# 1-Schematic_motor_starter_pcb_design.net
KiCad netlist of a schematic drawn in EasyEDA
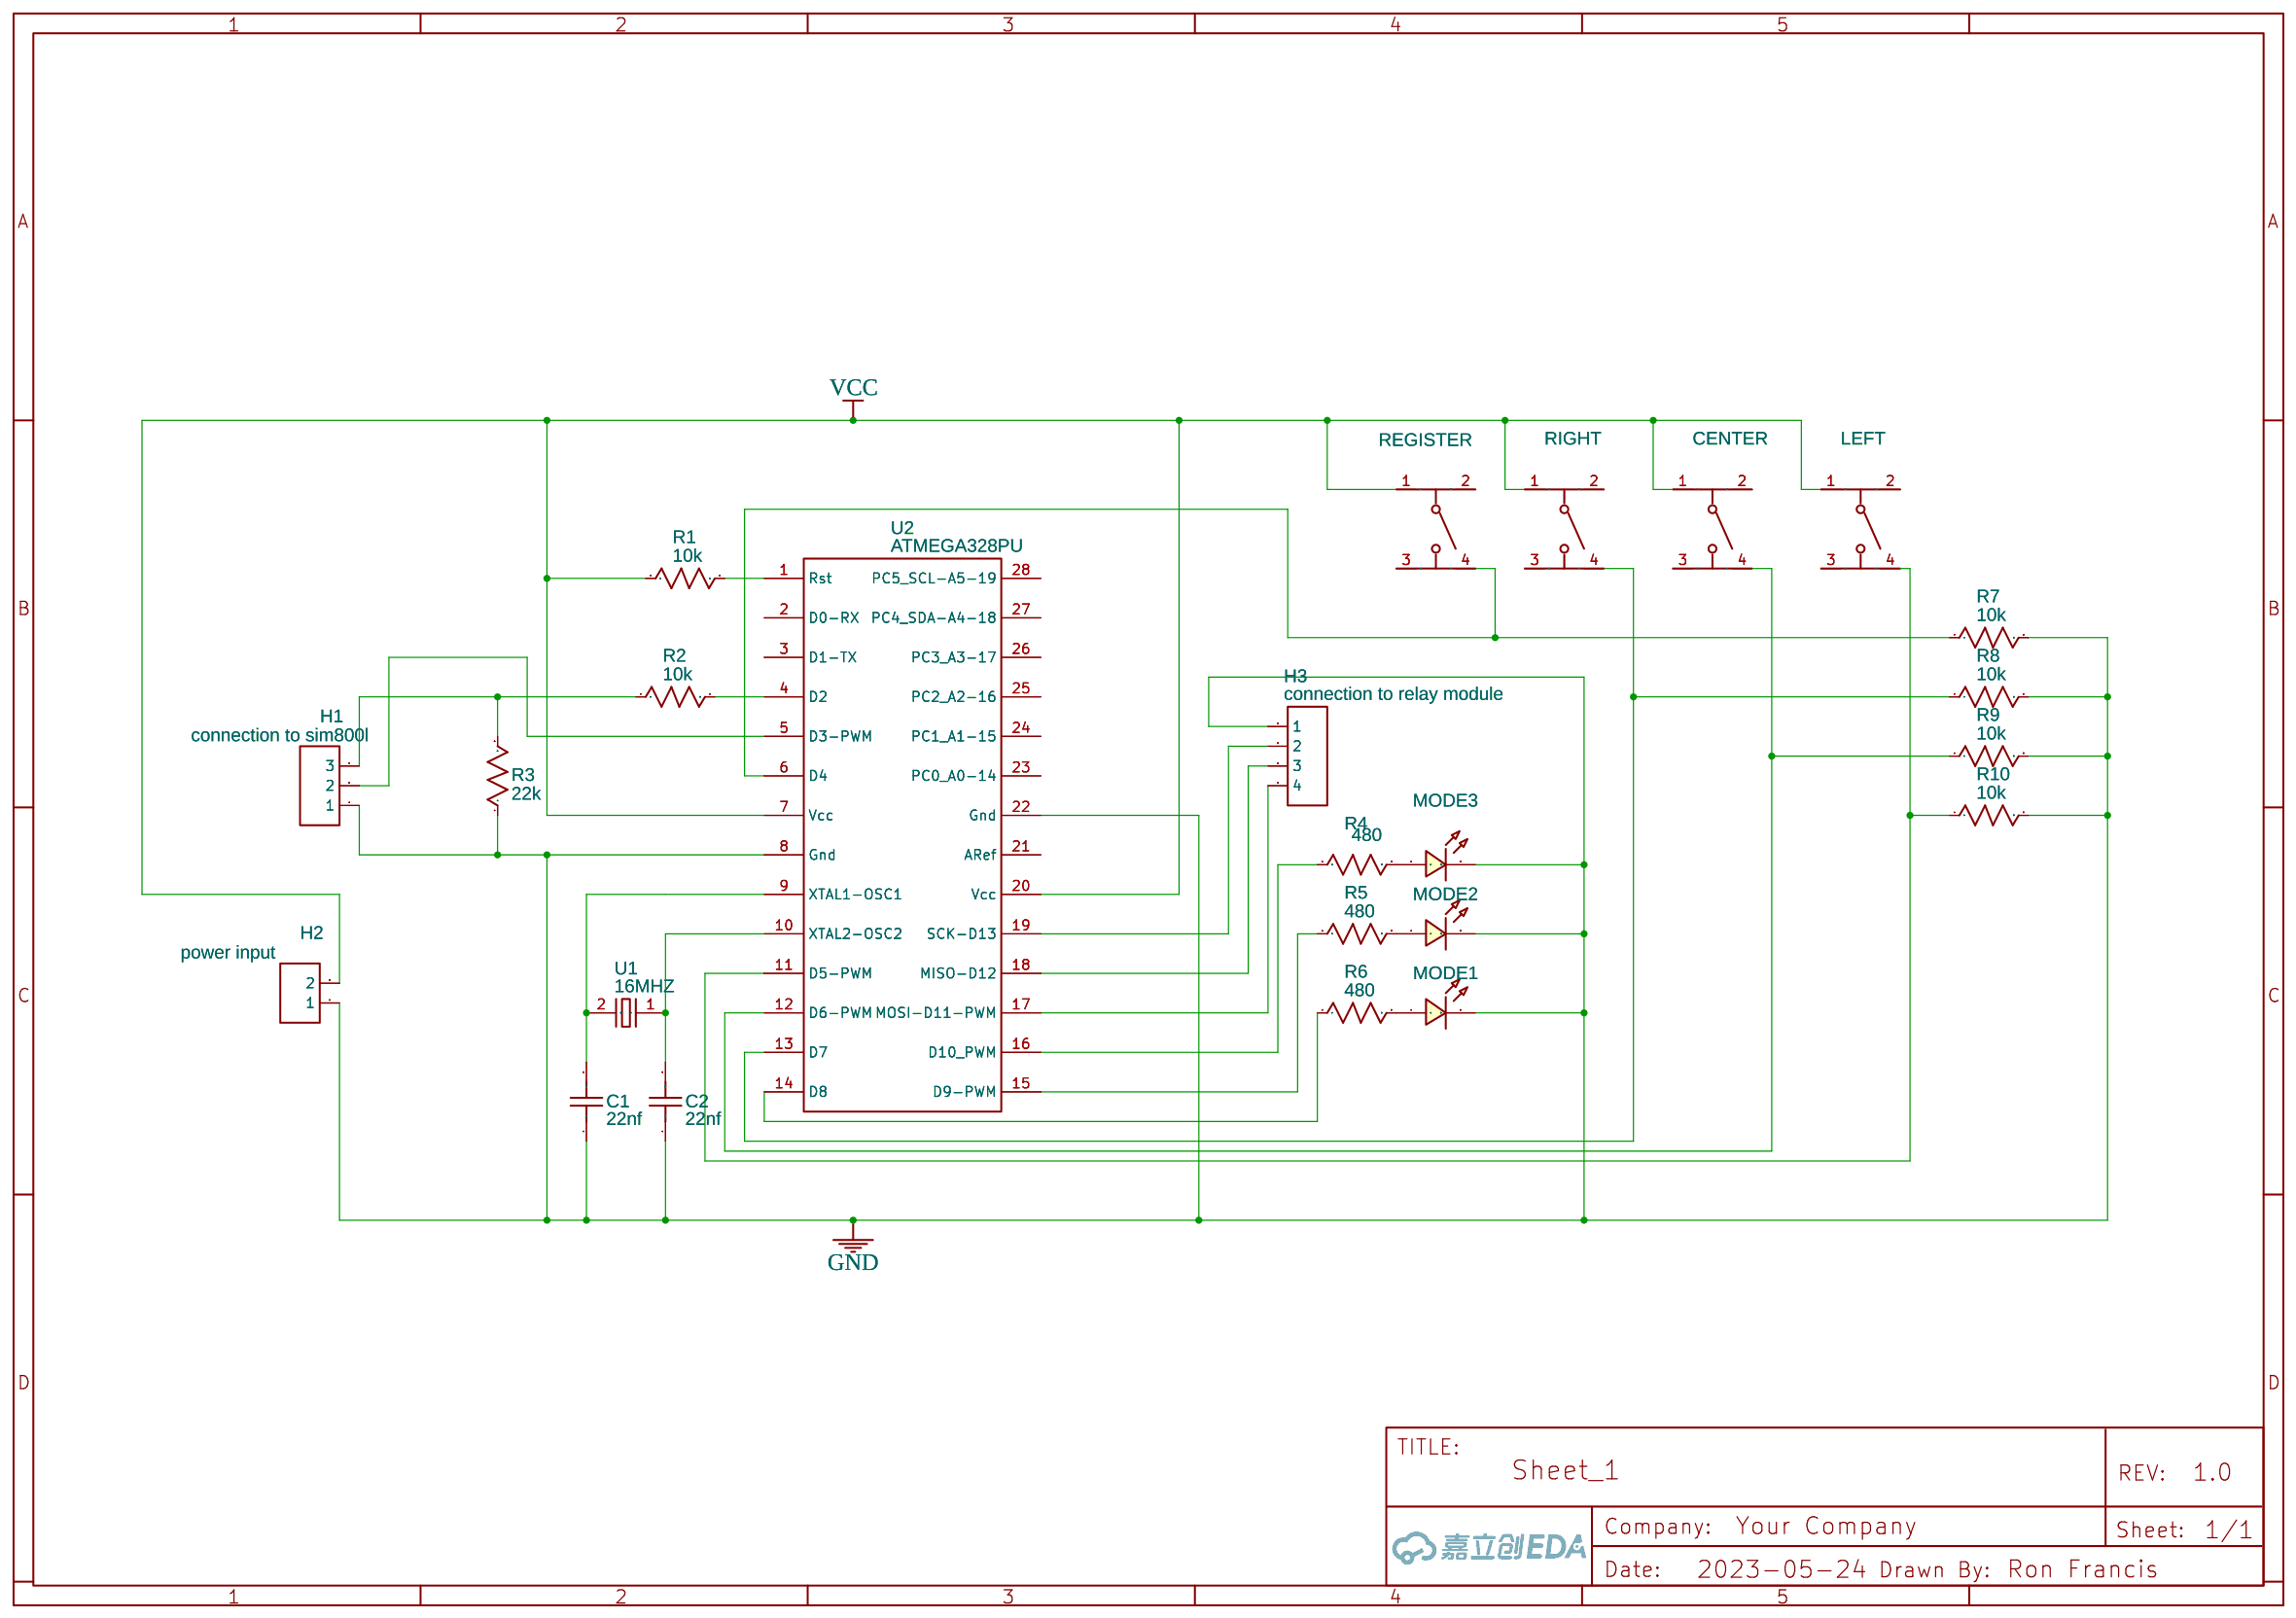
[diagram p0: schematic sheet]

(export (version "E")
  (design (tool "Eeschema 10.0.6"))
  (components
    (comp (ref "C1") (value "22nf") (libsource (lib "") (part "C_RAD-0.1_US")))
    (comp (ref "C2") (value "22nf") (libsource (lib "") (part "C_RAD-0.1_US")))
    (comp (ref "CENTER")
      (value "Button-SMD-6×6×5mm")
      (fields
        (field (name "BOM_Manufacturer Part") "6×6×5mm RHOS")
        (field (name "BOM_Supplier Part") "C21456")
      )
      (libsource (lib "") (part "Button-SMD-6×6×5mm_2"))
    )
    (comp (ref "H1")
      (value "connection to sim800l")
      (fields (field (name "BOM_Supplier Part") "C146690"))
      (libsource (lib "") (part "HDR-F-2.54_1x3"))
    )
    (comp (ref "H2")
      (value "power input")
      (fields (field (name "BOM_Supplier Part") "C49661"))
      (libsource (lib "") (part "HDR-F-2.54_1x2"))
    )
    (comp (ref "H3")
      (value "connection to relay module")
      (fields (field (name "BOM_Supplier Part") "C225501"))
      (libsource (lib "") (part "HDR-F-2.54_1x4"))
    )
    (comp (ref "LEFT")
      (value "Button-SMD-6×6×5mm")
      (fields
        (field (name "BOM_Manufacturer Part") "6×6×5mm RHOS")
        (field (name "BOM_Supplier Part") "C21456")
      )
      (libsource (lib "") (part "Button-SMD-6×6×5mm_1"))
    )
    (comp (ref "MODE1")
      (value "LED-TH-5mm_R")
      (fields
        (field (name "BOM_Manufacturer Part") "333-2SURD/S530-A3")
        (field (name "BOM_Supplier Part") "C87271")
      )
      (libsource (lib "") (part "LED-TH-5mm_R"))
    )
    (comp (ref "MODE2")
      (value "LED-TH-5mm_R")
      (fields
        (field (name "BOM_Manufacturer Part") "333-2SURD/S530-A3")
        (field (name "BOM_Supplier Part") "C87271")
      )
      (libsource (lib "") (part "LED-TH-5mm_R"))
    )
    (comp (ref "MODE3")
      (value "LED-TH-5mm_R")
      (fields
        (field (name "BOM_Manufacturer Part") "333-2SURD/S530-A3")
        (field (name "BOM_Supplier Part") "C87271")
      )
      (libsource (lib "") (part "LED-TH-5mm_R"))
    )
    (comp (ref "R1") (value "10k") (libsource (lib "") (part "R_AXIAL-0.4_US")))
    (comp (ref "R2") (value "10k") (libsource (lib "") (part "R_AXIAL-0.4_US")))
    (comp (ref "R3") (value "22k") (libsource (lib "") (part "R_AXIAL-0.4_US_1")))
    (comp (ref "R4") (value "480") (libsource (lib "") (part "R_AXIAL-0.4_US")))
    (comp (ref "R5") (value "480") (libsource (lib "") (part "R_AXIAL-0.4_US")))
    (comp (ref "R6") (value "480") (libsource (lib "") (part "R_AXIAL-0.4_US")))
    (comp (ref "R7") (value "10k") (libsource (lib "") (part "R_AXIAL-0.4_US")))
    (comp (ref "R8") (value "10k") (libsource (lib "") (part "R_AXIAL-0.4_US")))
    (comp (ref "R9") (value "10k") (libsource (lib "") (part "R_AXIAL-0.4_US")))
    (comp (ref "R10") (value "10k") (libsource (lib "") (part "R_AXIAL-0.4_US")))
    (comp (ref "REGISTER")
      (value "Button-SMD-6×6×5mm")
      (fields
        (field (name "BOM_Manufacturer Part") "6×6×5mm RHOS")
        (field (name "BOM_Supplier Part") "C21456")
      )
      (libsource (lib "") (part "Button-SMD-6×6×5mm"))
    )
    (comp (ref "RIGHT")
      (value "Button-SMD-6×6×5mm")
      (fields
        (field (name "BOM_Manufacturer Part") "6×6×5mm RHOS")
        (field (name "BOM_Supplier Part") "C21456")
      )
      (libsource (lib "") (part "Button-SMD-6×6×5mm_3"))
    )
    (comp (ref "U1")
      (value "16MHZ")
      (fields (field (name "BOM_Supplier Part") "C9900024699"))
      (libsource (lib "") (part "16MHZ_C9900024699"))
    )
    (comp (ref "U2") (value "ATMEGA328PU") (libsource (lib "") (part "ATMEGA328PU")))
  )
  (nets
    (net (code "1") (name "GND") (class "Default")
      (node (ref "C1") (pin "1") (pinfunction "1_1") (pintype "unspecified"))
      (node (ref "C2") (pin "1") (pinfunction "1_1") (pintype "unspecified"))
      (node (ref "H1") (pin "1") (pinfunction "1_1") (pintype "input"))
      (node (ref "H2") (pin "1") (pinfunction "1_1") (pintype "input"))
      (node (ref "H3") (pin "1") (pinfunction "1_1") (pintype "unspecified"))
      (node (ref "MODE1") (pin "2") (pinfunction "2_2") (pintype "unspecified"))
      (node (ref "MODE2") (pin "2") (pinfunction "2_2") (pintype "unspecified"))
      (node (ref "MODE3") (pin "2") (pinfunction "2_2") (pintype "unspecified"))
      (node (ref "R10") (pin "2") (pinfunction "2_2") (pintype "unspecified"))
      (node (ref "R3") (pin "1") (pinfunction "1_1") (pintype "unspecified"))
      (node (ref "R7") (pin "2") (pinfunction "2_2") (pintype "unspecified"))
      (node (ref "R8") (pin "2") (pinfunction "2_2") (pintype "unspecified"))
      (node (ref "R9") (pin "2") (pinfunction "2_2") (pintype "unspecified"))
      (node (ref "U2") (pin "22") (pinfunction "Gnd_22") (pintype "unspecified"))
      (node (ref "U2") (pin "8") (pinfunction "Gnd_8") (pintype "unspecified"))
    )
    (net (code "2") (name "Net-(H1-Pad3)") (class "Default")
      (node (ref "H1") (pin "3") (pinfunction "3_3") (pintype "input"))
      (node (ref "R2") (pin "1") (pinfunction "1_1") (pintype "unspecified"))
      (node (ref "R3") (pin "2") (pinfunction "2_2") (pintype "unspecified"))
    )
    (net (code "3") (name "Net-(MODE1-Pad1)") (class "Default")
      (node (ref "MODE1") (pin "1") (pinfunction "1_1") (pintype "unspecified"))
      (node (ref "R6") (pin "2") (pinfunction "2_2") (pintype "unspecified"))
    )
    (net (code "4") (name "Net-(MODE2-Pad1)") (class "Default")
      (node (ref "MODE2") (pin "1") (pinfunction "1_1") (pintype "unspecified"))
      (node (ref "R5") (pin "2") (pinfunction "2_2") (pintype "unspecified"))
    )
    (net (code "5") (name "Net-(MODE3-Pad1)") (class "Default")
      (node (ref "MODE3") (pin "1") (pinfunction "1_1") (pintype "unspecified"))
      (node (ref "R4") (pin "2") (pinfunction "2_2") (pintype "unspecified"))
    )
    (net (code "6") (name "Net-(U2-D2)") (class "Default")
      (node (ref "R2") (pin "2") (pinfunction "2_2") (pintype "unspecified"))
      (node (ref "U2") (pin "4") (pinfunction "D2_4") (pintype "unspecified"))
    )
    (net (code "7") (name "Net-(U2-D3-PWM)") (class "Default")
      (node (ref "H1") (pin "2") (pinfunction "2_2") (pintype "input"))
      (node (ref "U2") (pin "5") (pinfunction "D3-PWM_5") (pintype "unspecified"))
    )
    (net (code "8") (name "Net-(U2-D4)") (class "Default")
      (node (ref "R7") (pin "1") (pinfunction "1_1") (pintype "unspecified"))
      (node (ref "REGISTER") (pin "4") (pinfunction "4_4") (pintype "unspecified"))
      (node (ref "U2") (pin "6") (pinfunction "D4_6") (pintype "unspecified"))
    )
    (net (code "9") (name "Net-(U2-D5-PWM)") (class "Default")
      (node (ref "LEFT") (pin "4") (pinfunction "4_4") (pintype "unspecified"))
      (node (ref "R10") (pin "1") (pinfunction "1_1") (pintype "unspecified"))
      (node (ref "U2") (pin "11") (pinfunction "D5-PWM_11") (pintype "unspecified"))
    )
    (net (code "10") (name "Net-(U2-D6-PWM)") (class "Default")
      (node (ref "CENTER") (pin "4") (pinfunction "4_4") (pintype "unspecified"))
      (node (ref "R9") (pin "1") (pinfunction "1_1") (pintype "unspecified"))
      (node (ref "U2") (pin "12") (pinfunction "D6-PWM_12") (pintype "unspecified"))
    )
    (net (code "11") (name "Net-(U2-D7)") (class "Default")
      (node (ref "R8") (pin "1") (pinfunction "1_1") (pintype "unspecified"))
      (node (ref "RIGHT") (pin "4") (pinfunction "4_4") (pintype "unspecified"))
      (node (ref "U2") (pin "13") (pinfunction "D7_13") (pintype "unspecified"))
    )
    (net (code "12") (name "Net-(U2-D8)") (class "Default")
      (node (ref "R6") (pin "1") (pinfunction "1_1") (pintype "unspecified"))
      (node (ref "U2") (pin "14") (pinfunction "D8_14") (pintype "unspecified"))
    )
    (net (code "13") (name "Net-(U2-D9-PWM)") (class "Default")
      (node (ref "R5") (pin "1") (pinfunction "1_1") (pintype "unspecified"))
      (node (ref "U2") (pin "15") (pinfunction "D9-PWM_15") (pintype "unspecified"))
    )
    (net (code "14") (name "Net-(U2-D10_PWM)") (class "Default")
      (node (ref "R4") (pin "1") (pinfunction "1_1") (pintype "unspecified"))
      (node (ref "U2") (pin "16") (pinfunction "D10_PWM_16") (pintype "unspecified"))
    )
    (net (code "15") (name "Net-(U2-MISO-D12)") (class "Default")
      (node (ref "H3") (pin "3") (pinfunction "3_3") (pintype "unspecified"))
      (node (ref "U2") (pin "18") (pinfunction "MISO-D12_18") (pintype "unspecified"))
    )
    (net (code "16") (name "Net-(U2-MOSI-D11-PWM)") (class "Default")
      (node (ref "H3") (pin "4") (pinfunction "4_4") (pintype "unspecified"))
      (node (ref "U2") (pin "17") (pinfunction "MOSI-D11-PWM_17") (pintype "unspecified"))
    )
    (net (code "17") (name "Net-(U2-Rst)") (class "Default")
      (node (ref "R1") (pin "2") (pinfunction "2_2") (pintype "unspecified"))
      (node (ref "U2") (pin "1") (pinfunction "Rst_1") (pintype "unspecified"))
    )
    (net (code "18") (name "Net-(U2-SCK-D13)") (class "Default")
      (node (ref "H3") (pin "2") (pinfunction "2_2") (pintype "unspecified"))
      (node (ref "U2") (pin "19") (pinfunction "SCK-D13_19") (pintype "unspecified"))
    )
    (net (code "19") (name "Net-(U2-XTAL1-OSC1)") (class "Default")
      (node (ref "C1") (pin "2") (pinfunction "2_2") (pintype "unspecified"))
      (node (ref "U1") (pin "2") (pinfunction "2_2") (pintype "input"))
      (node (ref "U2") (pin "9") (pinfunction "XTAL1-OSC1_9") (pintype "unspecified"))
    )
    (net (code "20") (name "Net-(U2-XTAL2-OSC2)") (class "Default")
      (node (ref "C2") (pin "2") (pinfunction "2_2") (pintype "unspecified"))
      (node (ref "U1") (pin "1") (pinfunction "1_1") (pintype "input"))
      (node (ref "U2") (pin "10") (pinfunction "XTAL2-OSC2_10") (pintype "unspecified"))
    )
    (net (code "21") (name "VCC") (class "Default")
      (node (ref "CENTER") (pin "1") (pinfunction "1_1") (pintype "unspecified"))
      (node (ref "H2") (pin "2") (pinfunction "2_2") (pintype "input"))
      (node (ref "LEFT") (pin "1") (pinfunction "1_1") (pintype "unspecified"))
      (node (ref "R1") (pin "1") (pinfunction "1_1") (pintype "unspecified"))
      (node (ref "REGISTER") (pin "1") (pinfunction "1_1") (pintype "unspecified"))
      (node (ref "RIGHT") (pin "1") (pinfunction "1_1") (pintype "unspecified"))
      (node (ref "U2") (pin "20") (pinfunction "Vcc_20") (pintype "unspecified"))
      (node (ref "U2") (pin "7") (pinfunction "Vcc_7") (pintype "unspecified"))
    )
    (net (code "22") (name "unconnected-(CENTER-Pad2)") (class "Default")
      (node (ref "CENTER") (pin "2") (pinfunction "2_2") (pintype "unspecified"))
    )
    (net (code "23") (name "unconnected-(CENTER-Pad3)") (class "Default")
      (node (ref "CENTER") (pin "3") (pinfunction "3_3") (pintype "unspecified"))
    )
    (net (code "24") (name "unconnected-(LEFT-Pad2)") (class "Default")
      (node (ref "LEFT") (pin "2") (pinfunction "2_2") (pintype "unspecified"))
    )
    (net (code "25") (name "unconnected-(LEFT-Pad3)") (class "Default")
      (node (ref "LEFT") (pin "3") (pinfunction "3_3") (pintype "unspecified"))
    )
    (net (code "26") (name "unconnected-(REGISTER-Pad2)") (class "Default")
      (node (ref "REGISTER") (pin "2") (pinfunction "2_2") (pintype "unspecified"))
    )
    (net (code "27") (name "unconnected-(REGISTER-Pad3)") (class "Default")
      (node (ref "REGISTER") (pin "3") (pinfunction "3_3") (pintype "unspecified"))
    )
    (net (code "28") (name "unconnected-(RIGHT-Pad2)") (class "Default")
      (node (ref "RIGHT") (pin "2") (pinfunction "2_2") (pintype "unspecified"))
    )
    (net (code "29") (name "unconnected-(RIGHT-Pad3)") (class "Default")
      (node (ref "RIGHT") (pin "3") (pinfunction "3_3") (pintype "unspecified"))
    )
    (net (code "30") (name "unconnected-(U2-ARef-Pad21)") (class "Default")
      (node (ref "U2") (pin "21") (pinfunction "ARef_21") (pintype "unspecified"))
    )
    (net (code "31") (name "unconnected-(U2-D0-RX-Pad2)") (class "Default")
      (node (ref "U2") (pin "2") (pinfunction "D0-RX_2") (pintype "unspecified"))
    )
    (net (code "32") (name "unconnected-(U2-D1-TX-Pad3)") (class "Default")
      (node (ref "U2") (pin "3") (pinfunction "D1-TX_3") (pintype "unspecified"))
    )
    (net (code "33") (name "unconnected-(U2-PC0_A0-14-Pad23)") (class "Default")
      (node (ref "U2") (pin "23") (pinfunction "PC0_A0-14_23") (pintype "unspecified"))
    )
    (net (code "34") (name "unconnected-(U2-PC1_A1-15-Pad24)") (class "Default")
      (node (ref "U2") (pin "24") (pinfunction "PC1_A1-15_24") (pintype "unspecified"))
    )
    (net (code "35") (name "unconnected-(U2-PC2_A2-16-Pad25)") (class "Default")
      (node (ref "U2") (pin "25") (pinfunction "PC2_A2-16_25") (pintype "unspecified"))
    )
    (net (code "36") (name "unconnected-(U2-PC3_A3-17-Pad26)") (class "Default")
      (node (ref "U2") (pin "26") (pinfunction "PC3_A3-17_26") (pintype "unspecified"))
    )
    (net (code "37") (name "unconnected-(U2-PC4_SDA-A4-18-Pad27)") (class "Default")
      (node (ref "U2") (pin "27") (pinfunction "PC4_SDA-A4-18_27") (pintype "unspecified"))
    )
    (net (code "38") (name "unconnected-(U2-PC5_SCL-A5-19-Pad28)") (class "Default")
      (node (ref "U2") (pin "28") (pinfunction "PC5_SCL-A5-19_28") (pintype "unspecified"))
    )
  )
)
